# cnc-distributor.net
KiCad netlist of a schematic drawn in EAGLE
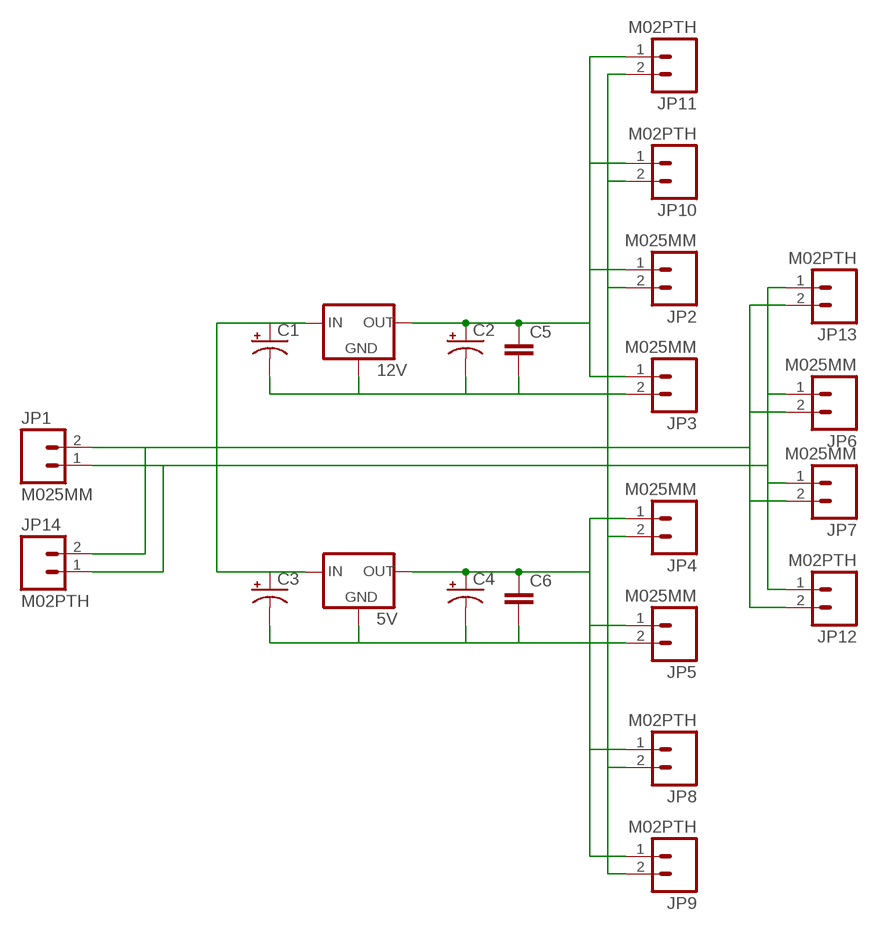
[diagram p0: schematic, sheet 1]

(export (version "E")
  (design (tool "Eeschema 10.0.6"))
  (components
    (comp (ref "5V")
      (value "78XXS")
      (footprint "eagle-import:78XXS")
      (libsource (lib "eagle-import") (part "78XXS"))
    )
    (comp (ref "12V")
      (value "78XXS")
      (footprint "eagle-import:78XXS")
      (libsource (lib "eagle-import") (part "78XXS"))
    )
    (comp (ref "C1")
      (value "CAP_POLPTH2")
      (footprint "eagle-import:CPOL-RADIAL-10UF-25V")
      (libsource (lib "eagle-import") (part "CAP_POLPTH2"))
    )
    (comp (ref "C2")
      (value "CAP_POLPTH2")
      (footprint "eagle-import:CPOL-RADIAL-10UF-25V")
      (libsource (lib "eagle-import") (part "CAP_POLPTH2"))
    )
    (comp (ref "C3")
      (value "CAP_POLPTH2")
      (footprint "eagle-import:CPOL-RADIAL-10UF-25V")
      (libsource (lib "eagle-import") (part "CAP_POLPTH2"))
    )
    (comp (ref "C4")
      (value "CAP_POLPTH2")
      (footprint "eagle-import:CPOL-RADIAL-10UF-25V")
      (libsource (lib "eagle-import") (part "CAP_POLPTH2"))
    )
    (comp (ref "C5")
      (value "CAPPTH2")
      (footprint "eagle-import:CAP-PTH-SMALL2")
      (libsource (lib "eagle-import") (part "CAPPTH2"))
    )
    (comp (ref "C6")
      (value "CAPPTH2")
      (footprint "eagle-import:CAP-PTH-SMALL2")
      (libsource (lib "eagle-import") (part "CAPPTH2"))
    )
    (comp (ref "JP1")
      (value "M025MM")
      (footprint "eagle-import:SCREWTERMINAL-5MM-2")
      (libsource (lib "eagle-import") (part "M025MM"))
    )
    (comp (ref "JP2")
      (value "M025MM")
      (footprint "eagle-import:SCREWTERMINAL-5MM-2")
      (libsource (lib "eagle-import") (part "M025MM"))
    )
    (comp (ref "JP3")
      (value "M025MM")
      (footprint "eagle-import:SCREWTERMINAL-5MM-2")
      (libsource (lib "eagle-import") (part "M025MM"))
    )
    (comp (ref "JP4")
      (value "M025MM")
      (footprint "eagle-import:SCREWTERMINAL-5MM-2")
      (libsource (lib "eagle-import") (part "M025MM"))
    )
    (comp (ref "JP5")
      (value "M025MM")
      (footprint "eagle-import:SCREWTERMINAL-5MM-2")
      (libsource (lib "eagle-import") (part "M025MM"))
    )
    (comp (ref "JP6")
      (value "M025MM")
      (footprint "eagle-import:SCREWTERMINAL-5MM-2")
      (libsource (lib "eagle-import") (part "M025MM"))
    )
    (comp (ref "JP7")
      (value "M025MM")
      (footprint "eagle-import:SCREWTERMINAL-5MM-2")
      (libsource (lib "eagle-import") (part "M025MM"))
    )
    (comp (ref "JP8")
      (value "M02PTH")
      (footprint "eagle-import:1X02")
      (libsource (lib "eagle-import") (part "M02PTH"))
    )
    (comp (ref "JP9")
      (value "M02PTH")
      (footprint "eagle-import:1X02")
      (libsource (lib "eagle-import") (part "M02PTH"))
    )
    (comp (ref "JP10")
      (value "M02PTH")
      (footprint "eagle-import:1X02")
      (libsource (lib "eagle-import") (part "M02PTH"))
    )
    (comp (ref "JP11")
      (value "M02PTH")
      (footprint "eagle-import:1X02")
      (libsource (lib "eagle-import") (part "M02PTH"))
    )
    (comp (ref "JP12")
      (value "M02PTH")
      (footprint "eagle-import:1X02")
      (libsource (lib "eagle-import") (part "M02PTH"))
    )
    (comp (ref "JP13")
      (value "M02PTH")
      (footprint "eagle-import:1X02")
      (libsource (lib "eagle-import") (part "M02PTH"))
    )
    (comp (ref "JP14")
      (value "M02PTH")
      (footprint "eagle-import:1X02")
      (libsource (lib "eagle-import") (part "M02PTH"))
    )
  )
  (nets
    (net (code "1") (name "Net-(C1-+)") (class "Default")
      (node (ref "12V") (pin "IN") (pinfunction "IN_IN") (pintype "input"))
      (node (ref "5V") (pin "IN") (pinfunction "IN_IN") (pintype "input"))
      (node (ref "C1") (pin "1") (pinfunction "+_1") (pintype "passive"))
      (node (ref "C3") (pin "1") (pinfunction "+_1") (pintype "passive"))
      (node (ref "JP1") (pin "1") (pinfunction "1_1") (pintype "passive"))
      (node (ref "JP12") (pin "1") (pinfunction "1_1") (pintype "passive"))
      (node (ref "JP13") (pin "1") (pinfunction "1_1") (pintype "passive"))
      (node (ref "JP14") (pin "1") (pinfunction "1_1") (pintype "passive"))
      (node (ref "JP6") (pin "1") (pinfunction "1_1") (pintype "passive"))
      (node (ref "JP7") (pin "1") (pinfunction "1_1") (pintype "passive"))
    )
    (net (code "2") (name "Net-(C1--)") (class "Default")
      (node (ref "12V") (pin "GND") (pinfunction "GND_GND") (pintype "input"))
      (node (ref "5V") (pin "GND") (pinfunction "GND_GND") (pintype "input"))
      (node (ref "C1") (pin "2") (pinfunction "-_2") (pintype "passive"))
      (node (ref "C2") (pin "2") (pinfunction "-_2") (pintype "passive"))
      (node (ref "C3") (pin "2") (pinfunction "-_2") (pintype "passive"))
      (node (ref "C4") (pin "2") (pinfunction "-_2") (pintype "passive"))
      (node (ref "C5") (pin "2") (pinfunction "2_2") (pintype "passive"))
      (node (ref "C6") (pin "2") (pinfunction "2_2") (pintype "passive"))
      (node (ref "JP1") (pin "2") (pinfunction "2_2") (pintype "passive"))
      (node (ref "JP10") (pin "2") (pinfunction "2_2") (pintype "passive"))
      (node (ref "JP11") (pin "2") (pinfunction "2_2") (pintype "passive"))
      (node (ref "JP12") (pin "2") (pinfunction "2_2") (pintype "passive"))
      (node (ref "JP13") (pin "2") (pinfunction "2_2") (pintype "passive"))
      (node (ref "JP14") (pin "2") (pinfunction "2_2") (pintype "passive"))
      (node (ref "JP2") (pin "2") (pinfunction "2_2") (pintype "passive"))
      (node (ref "JP3") (pin "2") (pinfunction "2_2") (pintype "passive"))
      (node (ref "JP4") (pin "2") (pinfunction "2_2") (pintype "passive"))
      (node (ref "JP5") (pin "2") (pinfunction "2_2") (pintype "passive"))
      (node (ref "JP6") (pin "2") (pinfunction "2_2") (pintype "passive"))
      (node (ref "JP7") (pin "2") (pinfunction "2_2") (pintype "passive"))
      (node (ref "JP8") (pin "2") (pinfunction "2_2") (pintype "passive"))
      (node (ref "JP9") (pin "2") (pinfunction "2_2") (pintype "passive"))
    )
    (net (code "3") (name "Net-(C2-+)") (class "Default")
      (node (ref "12V") (pin "OUT") (pinfunction "OUT_OUT") (pintype "passive"))
      (node (ref "C2") (pin "1") (pinfunction "+_1") (pintype "passive"))
      (node (ref "C5") (pin "1") (pinfunction "1_1") (pintype "passive"))
      (node (ref "JP10") (pin "1") (pinfunction "1_1") (pintype "passive"))
      (node (ref "JP11") (pin "1") (pinfunction "1_1") (pintype "passive"))
      (node (ref "JP2") (pin "1") (pinfunction "1_1") (pintype "passive"))
      (node (ref "JP3") (pin "1") (pinfunction "1_1") (pintype "passive"))
    )
    (net (code "4") (name "Net-(C4-+)") (class "Default")
      (node (ref "5V") (pin "OUT") (pinfunction "OUT_OUT") (pintype "passive"))
      (node (ref "C4") (pin "1") (pinfunction "+_1") (pintype "passive"))
      (node (ref "C6") (pin "1") (pinfunction "1_1") (pintype "passive"))
      (node (ref "JP4") (pin "1") (pinfunction "1_1") (pintype "passive"))
      (node (ref "JP5") (pin "1") (pinfunction "1_1") (pintype "passive"))
      (node (ref "JP8") (pin "1") (pinfunction "1_1") (pintype "passive"))
      (node (ref "JP9") (pin "1") (pinfunction "1_1") (pintype "passive"))
    )
  )
)
